# PowerManagement_Driver.net
KiCad netlist of a schematic drawn in Altium Designer
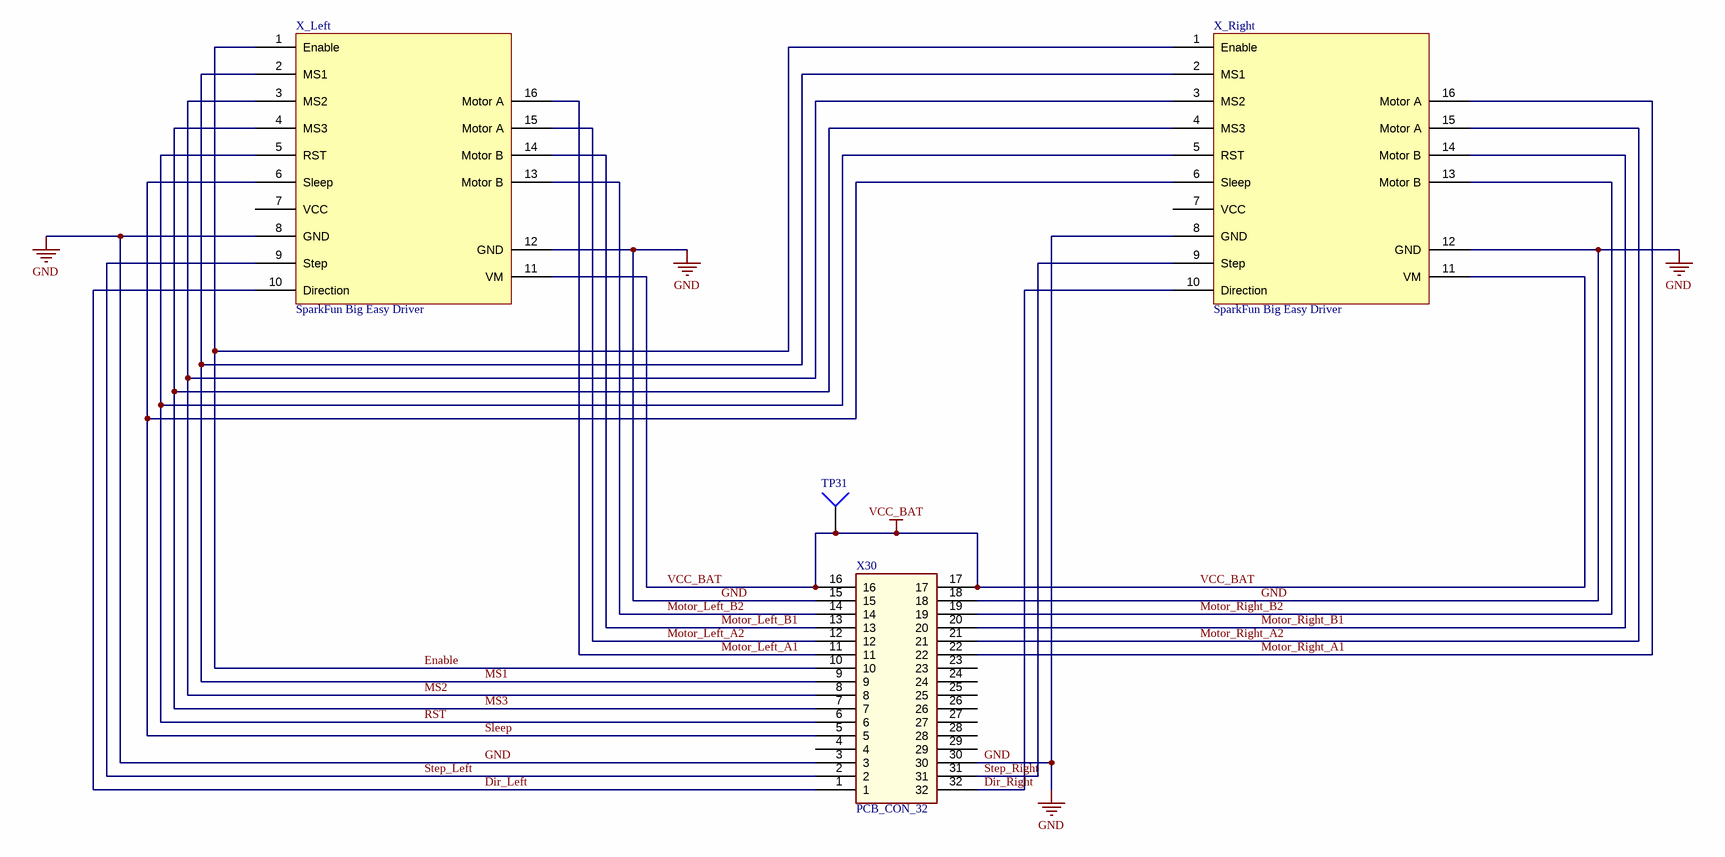
[diagram p0: PowerManagement_Driver.SchDoc]

(export (version "E")
  (design (tool "Eeschema 10.0.6"))
  (components
    (comp (ref "TP31")
      (value "~")
      (footprint "PIN1")
      (fields (field (name "PUBLISHER") "Altium Limited"))
      (libsource (lib "Miscellaneous Connectors") (part "Socket"))
    )
    (comp (ref "X30")
      (value "PCB_CON_32")
      (footprint "PCB_CON_32_PLUG")
      (description "Connects a PCB with another. This scheme is either jack or plug, depends on footprint")
      (libsource (lib "PREN2Lib") (part "PCB_CON_32"))
    )
    (comp (ref "X_Left")
      (value "SparkFun Big Easy Driver")
      (footprint "SPARKFUN_BIG_EASY_DRIVER")
      (description "Stepper Motor Driver with 4 wires")
      (libsource (lib "PREN2Lib") (part "SparkFun Big Easy Driver"))
    )
    (comp (ref "X_Right")
      (value "SparkFun Big Easy Driver")
      (footprint "SPARKFUN_BIG_EASY_DRIVER")
      (description "Stepper Motor Driver with 4 wires")
      (libsource (lib "PREN2Lib") (part "SparkFun Big Easy Driver"))
    )
  )
  (nets
    (net (code "1") (name "/Dir_Left") (class "Default")
      (node (ref "X30") (pin "1") (pinfunction "1_1") (pintype "passive"))
      (node (ref "X_Left") (pin "10") (pinfunction "Direction_10") (pintype "passive"))
    )
    (net (code "2") (name "/Dir_Right") (class "Default")
      (node (ref "X30") (pin "32") (pinfunction "32_32") (pintype "passive"))
      (node (ref "X_Right") (pin "10") (pinfunction "Direction_10") (pintype "passive"))
    )
    (net (code "3") (name "/Enable") (class "Default")
      (node (ref "X30") (pin "10") (pinfunction "10_10") (pintype "passive"))
      (node (ref "X_Left") (pin "1") (pinfunction "Enable_1") (pintype "passive"))
      (node (ref "X_Right") (pin "1") (pinfunction "Enable_1") (pintype "passive"))
    )
    (net (code "4") (name "/MS1") (class "Default")
      (node (ref "X30") (pin "9") (pinfunction "9_9") (pintype "passive"))
      (node (ref "X_Left") (pin "2") (pinfunction "MS1_2") (pintype "passive"))
      (node (ref "X_Right") (pin "2") (pinfunction "MS1_2") (pintype "passive"))
    )
    (net (code "5") (name "/MS2") (class "Default")
      (node (ref "X30") (pin "8") (pinfunction "8_8") (pintype "passive"))
      (node (ref "X_Left") (pin "3") (pinfunction "MS2_3") (pintype "passive"))
      (node (ref "X_Right") (pin "3") (pinfunction "MS2_3") (pintype "passive"))
    )
    (net (code "6") (name "/MS3") (class "Default")
      (node (ref "X30") (pin "7") (pinfunction "7_7") (pintype "passive"))
      (node (ref "X_Left") (pin "4") (pinfunction "MS3_4") (pintype "passive"))
      (node (ref "X_Right") (pin "4") (pinfunction "MS3_4") (pintype "passive"))
    )
    (net (code "7") (name "/Motor_Left_A1") (class "Default")
      (node (ref "X30") (pin "11") (pinfunction "11_11") (pintype "passive"))
      (node (ref "X_Left") (pin "16") (pinfunction "Motor_A_16") (pintype "passive"))
    )
    (net (code "8") (name "/Motor_Left_A2") (class "Default")
      (node (ref "X30") (pin "12") (pinfunction "12_12") (pintype "passive"))
      (node (ref "X_Left") (pin "15") (pinfunction "Motor_A_15") (pintype "passive"))
    )
    (net (code "9") (name "/Motor_Left_B1") (class "Default")
      (node (ref "X30") (pin "13") (pinfunction "13_13") (pintype "passive"))
      (node (ref "X_Left") (pin "14") (pinfunction "Motor_B_14") (pintype "passive"))
    )
    (net (code "10") (name "/Motor_Left_B2") (class "Default")
      (node (ref "X30") (pin "14") (pinfunction "14_14") (pintype "passive"))
      (node (ref "X_Left") (pin "13") (pinfunction "Motor_B_13") (pintype "passive"))
    )
    (net (code "11") (name "/Motor_Right_A1") (class "Default")
      (node (ref "X30") (pin "22") (pinfunction "22_22") (pintype "passive"))
      (node (ref "X_Right") (pin "16") (pinfunction "Motor_A_16") (pintype "passive"))
    )
    (net (code "12") (name "/Motor_Right_A2") (class "Default")
      (node (ref "X30") (pin "21") (pinfunction "21_21") (pintype "passive"))
      (node (ref "X_Right") (pin "15") (pinfunction "Motor_A_15") (pintype "passive"))
    )
    (net (code "13") (name "/Motor_Right_B1") (class "Default")
      (node (ref "X30") (pin "20") (pinfunction "20_20") (pintype "passive"))
      (node (ref "X_Right") (pin "14") (pinfunction "Motor_B_14") (pintype "passive"))
    )
    (net (code "14") (name "/Motor_Right_B2") (class "Default")
      (node (ref "X30") (pin "19") (pinfunction "19_19") (pintype "passive"))
      (node (ref "X_Right") (pin "13") (pinfunction "Motor_B_13") (pintype "passive"))
    )
    (net (code "15") (name "/RST") (class "Default")
      (node (ref "X30") (pin "6") (pinfunction "6_6") (pintype "passive"))
      (node (ref "X_Left") (pin "5") (pinfunction "RST_5") (pintype "passive"))
      (node (ref "X_Right") (pin "5") (pinfunction "RST_5") (pintype "passive"))
    )
    (net (code "16") (name "/Sleep") (class "Default")
      (node (ref "X30") (pin "5") (pinfunction "5_5") (pintype "passive"))
      (node (ref "X_Left") (pin "6") (pinfunction "Sleep_6") (pintype "passive"))
      (node (ref "X_Right") (pin "6") (pinfunction "Sleep_6") (pintype "passive"))
    )
    (net (code "17") (name "/Step_Left") (class "Default")
      (node (ref "X30") (pin "2") (pinfunction "2_2") (pintype "passive"))
      (node (ref "X_Left") (pin "9") (pinfunction "Step_9") (pintype "passive"))
    )
    (net (code "18") (name "/Step_Right") (class "Default")
      (node (ref "X30") (pin "31") (pinfunction "31_31") (pintype "passive"))
      (node (ref "X_Right") (pin "9") (pinfunction "Step_9") (pintype "passive"))
    )
    (net (code "19") (name "GND") (class "Default")
      (node (ref "X30") (pin "15") (pinfunction "15_15") (pintype "passive"))
      (node (ref "X30") (pin "18") (pinfunction "18_18") (pintype "passive"))
      (node (ref "X30") (pin "3") (pinfunction "3_3") (pintype "passive"))
      (node (ref "X30") (pin "30") (pinfunction "30_30") (pintype "passive"))
      (node (ref "X_Left") (pin "12") (pinfunction "GND_12") (pintype "passive"))
      (node (ref "X_Left") (pin "8") (pinfunction "GND_8") (pintype "passive"))
      (node (ref "X_Right") (pin "12") (pinfunction "GND_12") (pintype "passive"))
      (node (ref "X_Right") (pin "8") (pinfunction "GND_8") (pintype "passive"))
    )
    (net (code "20") (name "VCC_BAT") (class "Default")
      (node (ref "TP31") (pin "1") (pinfunction "1_1") (pintype "passive"))
      (node (ref "X30") (pin "16") (pinfunction "16_16") (pintype "passive"))
      (node (ref "X30") (pin "17") (pinfunction "17_17") (pintype "passive"))
      (node (ref "X_Left") (pin "11") (pinfunction "VM_11") (pintype "passive"))
      (node (ref "X_Right") (pin "11") (pinfunction "VM_11") (pintype "passive"))
    )
    (net (code "21") (name "unconnected-(X30-Pad4)") (class "Default")
      (node (ref "X30") (pin "4") (pinfunction "4_4") (pintype "passive"))
    )
    (net (code "22") (name "unconnected-(X30-Pad23)") (class "Default")
      (node (ref "X30") (pin "23") (pinfunction "23_23") (pintype "passive"))
    )
    (net (code "23") (name "unconnected-(X30-Pad24)") (class "Default")
      (node (ref "X30") (pin "24") (pinfunction "24_24") (pintype "passive"))
    )
    (net (code "24") (name "unconnected-(X30-Pad25)") (class "Default")
      (node (ref "X30") (pin "25") (pinfunction "25_25") (pintype "passive"))
    )
    (net (code "25") (name "unconnected-(X30-Pad26)") (class "Default")
      (node (ref "X30") (pin "26") (pinfunction "26_26") (pintype "passive"))
    )
    (net (code "26") (name "unconnected-(X30-Pad27)") (class "Default")
      (node (ref "X30") (pin "27") (pinfunction "27_27") (pintype "passive"))
    )
    (net (code "27") (name "unconnected-(X30-Pad28)") (class "Default")
      (node (ref "X30") (pin "28") (pinfunction "28_28") (pintype "passive"))
    )
    (net (code "28") (name "unconnected-(X30-Pad29)") (class "Default")
      (node (ref "X30") (pin "29") (pinfunction "29_29") (pintype "passive"))
    )
    (net (code "29") (name "unconnected-(X_Left-VCC-Pad7)") (class "Default")
      (node (ref "X_Left") (pin "7") (pinfunction "VCC_7") (pintype "passive"))
    )
    (net (code "30") (name "unconnected-(X_Right-VCC-Pad7)") (class "Default")
      (node (ref "X_Right") (pin "7") (pinfunction "VCC_7") (pintype "passive"))
    )
  )
)
